# LampenSteuerung_Driver.net
KiCad netlist of a schematic drawn in EAGLE
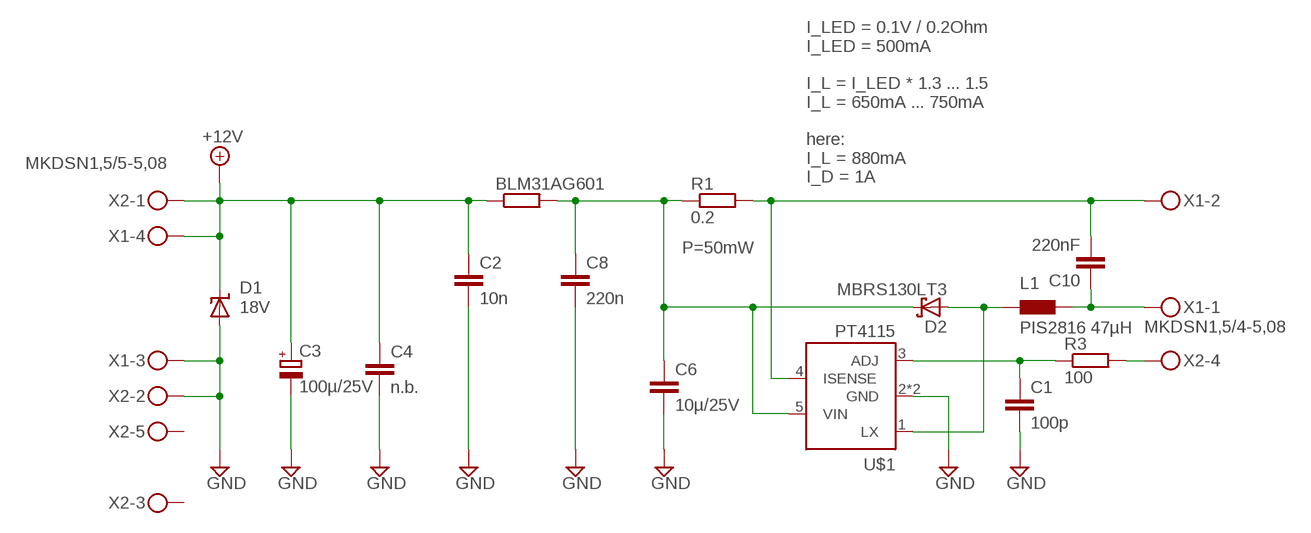
[diagram p0: schematic, sheet 1]

(export (version "E")
  (design (tool "Eeschema 10.0.6"))
  (components
    (comp (ref "BLM31AG601")
      (value "R-EU_R1206")
      (footprint "eagle-import:R1206")
      (libsource (lib "eagle-import") (part "R-EU_R1206"))
    )
    (comp (ref "C1")
      (value "100p")
      (footprint "eagle-import:C0603")
      (libsource (lib "eagle-import") (part "C-EUC0603"))
    )
    (comp (ref "C2")
      (value "10n")
      (footprint "eagle-import:C0603")
      (libsource (lib "eagle-import") (part "C-EUC0603"))
    )
    (comp (ref "C3")
      (value "100µ/25V")
      (footprint "eagle-import:E2,5-6")
      (libsource (lib "eagle-import") (part "CPOL-EUE2.5-6"))
    )
    (comp (ref "C4")
      (value "n.b.")
      (footprint "eagle-import:C1210")
      (libsource (lib "eagle-import") (part "C-EUC1210"))
    )
    (comp (ref "C6")
      (value "10µ/25V")
      (footprint "eagle-import:C1206")
      (libsource (lib "eagle-import") (part "C-EUC1206"))
    )
    (comp (ref "C8")
      (value "220n")
      (footprint "eagle-import:C0603")
      (libsource (lib "eagle-import") (part "C-EUC0603"))
    )
    (comp (ref "C10")
      (value "220nF")
      (footprint "eagle-import:C0603")
      (libsource (lib "eagle-import") (part "C-EUC0603"))
    )
    (comp (ref "D1")
      (value "18V")
      (footprint "eagle-import:SMBJ")
      (libsource (lib "eagle-import") (part "SUPPRESSOR-SMBJ"))
    )
    (comp (ref "D2")
      (value "MBRS130LT3")
      (footprint "eagle-import:SMB")
      (libsource (lib "eagle-import") (part "MBRS130LT3"))
    )
    (comp (ref "L1")
      (value "PIS2816 47µH")
      (footprint "eagle-import:PIS2816")
      (libsource (lib "eagle-import") (part "PIS2816"))
    )
    (comp (ref "R1")
      (value "0.2")
      (footprint "eagle-import:R1206")
      (libsource (lib "eagle-import") (part "R-EU_R1206"))
    )
    (comp (ref "R3")
      (value "100")
      (footprint "eagle-import:R1206")
      (libsource (lib "eagle-import") (part "R-EU_R1206"))
    )
    (comp (ref "U$1")
      (value "PT4115")
      (footprint "eagle-import:SOT89-5")
      (libsource (lib "eagle-import") (part "PT4115"))
    )
    (comp (ref "X1")
      (value "MKDSN1,5/4-5,08")
      (footprint "eagle-import:MKDSN1,5_4-5,08")
      (libsource (lib "eagle-import") (part "MKDSN1,5/4-5,08"))
    )
    (comp (ref "X2")
      (value "MKDSN1,5/5-5,08")
      (footprint "eagle-import:MKDSN1,5_5-5,08")
      (libsource (lib "eagle-import") (part "MKDSN1,5/5-5,08"))
    )
  )
  (nets
    (net (code "1") (name "+12V") (class "Default")
      (node (ref "BLM31AG601") (pin "1") (pinfunction "1_1") (pintype "passive"))
      (node (ref "C2") (pin "1") (pinfunction "1_1") (pintype "passive"))
      (node (ref "C3") (pin "+") (pinfunction "+_+") (pintype "passive"))
      (node (ref "C4") (pin "1") (pinfunction "1_1") (pintype "passive"))
      (node (ref "D1") (pin "C") (pinfunction "C_C") (pintype "passive"))
      (node (ref "X1") (pin "4") (pinfunction "KL_4") (pintype "passive"))
      (node (ref "X2") (pin "1") (pinfunction "KL_1") (pintype "passive"))
    )
    (net (code "2") (name "GND") (class "Default")
      (node (ref "C1") (pin "2") (pinfunction "2_2") (pintype "passive"))
      (node (ref "C2") (pin "2") (pinfunction "2_2") (pintype "passive"))
      (node (ref "C3") (pin "-") (pinfunction "-_-") (pintype "passive"))
      (node (ref "C4") (pin "2") (pinfunction "2_2") (pintype "passive"))
      (node (ref "C6") (pin "2") (pinfunction "2_2") (pintype "passive"))
      (node (ref "C8") (pin "2") (pinfunction "2_2") (pintype "passive"))
      (node (ref "D1") (pin "A") (pinfunction "A_A") (pintype "passive"))
      (node (ref "U$1") (pin "2") (pinfunction "GND_2") (pintype "power_in"))
      (node (ref "U$1") (pin "2.1") (pinfunction "GND_2.1") (pintype "power_in"))
      (node (ref "X1") (pin "3") (pinfunction "KL_3") (pintype "passive"))
      (node (ref "X2") (pin "2") (pinfunction "KL_2") (pintype "passive"))
    )
    (net (code "3") (name "Net-(U$1-ADJ)") (class "Default")
      (node (ref "C1") (pin "1") (pinfunction "1_1") (pintype "passive"))
      (node (ref "R3") (pin "1") (pinfunction "1_1") (pintype "passive"))
      (node (ref "U$1") (pin "3") (pinfunction "ADJ_3") (pintype "input"))
    )
    (net (code "4") (name "Net-(U$1-ISENSE)") (class "Default")
      (node (ref "C10") (pin "2") (pinfunction "2_2") (pintype "passive"))
      (node (ref "R1") (pin "2") (pinfunction "2_2") (pintype "passive"))
      (node (ref "U$1") (pin "4") (pinfunction "ISENSE_4") (pintype "input"))
      (node (ref "X1") (pin "2") (pinfunction "KL_2") (pintype "passive"))
    )
    (net (code "5") (name "Net-(U$1-LX)") (class "Default")
      (node (ref "D2") (pin "A") (pinfunction "A_A") (pintype "passive"))
      (node (ref "L1") (pin "P$1") (pinfunction "P$1_P$1") (pintype "bidirectional"))
      (node (ref "U$1") (pin "1") (pinfunction "LX_1") (pintype "output"))
    )
    (net (code "6") (name "Net-(U$1-VIN)") (class "Default")
      (node (ref "BLM31AG601") (pin "2") (pinfunction "2_2") (pintype "passive"))
      (node (ref "C6") (pin "1") (pinfunction "1_1") (pintype "passive"))
      (node (ref "C8") (pin "1") (pinfunction "1_1") (pintype "passive"))
      (node (ref "D2") (pin "C") (pinfunction "C_C") (pintype "passive"))
      (node (ref "R1") (pin "1") (pinfunction "1_1") (pintype "passive"))
      (node (ref "U$1") (pin "5") (pinfunction "VIN_5") (pintype "power_in"))
    )
    (net (code "7") (name "Net-(X1A-KL)") (class "Default")
      (node (ref "C10") (pin "1") (pinfunction "1_1") (pintype "passive"))
      (node (ref "L1") (pin "P$2") (pinfunction "P$2_P$2") (pintype "bidirectional"))
      (node (ref "X1") (pin "1") (pinfunction "KL_1") (pintype "passive"))
    )
    (net (code "8") (name "Net-(X2D-KL)") (class "Default")
      (node (ref "R3") (pin "2") (pinfunction "2_2") (pintype "passive"))
      (node (ref "X2") (pin "4") (pinfunction "KL_4") (pintype "passive"))
    )
    (net (code "9") (name "unconnected-(X2C-KL-Pad3)") (class "Default")
      (node (ref "X2") (pin "3") (pinfunction "KL_3") (pintype "passive"))
    )
    (net (code "10") (name "unconnected-(X2E-KL-Pad5)") (class "Default")
      (node (ref "X2") (pin "5") (pinfunction "KL_5") (pintype "passive"))
    )
  )
)
